# circuit.net
KiCad netlist of a schematic drawn in EAGLE
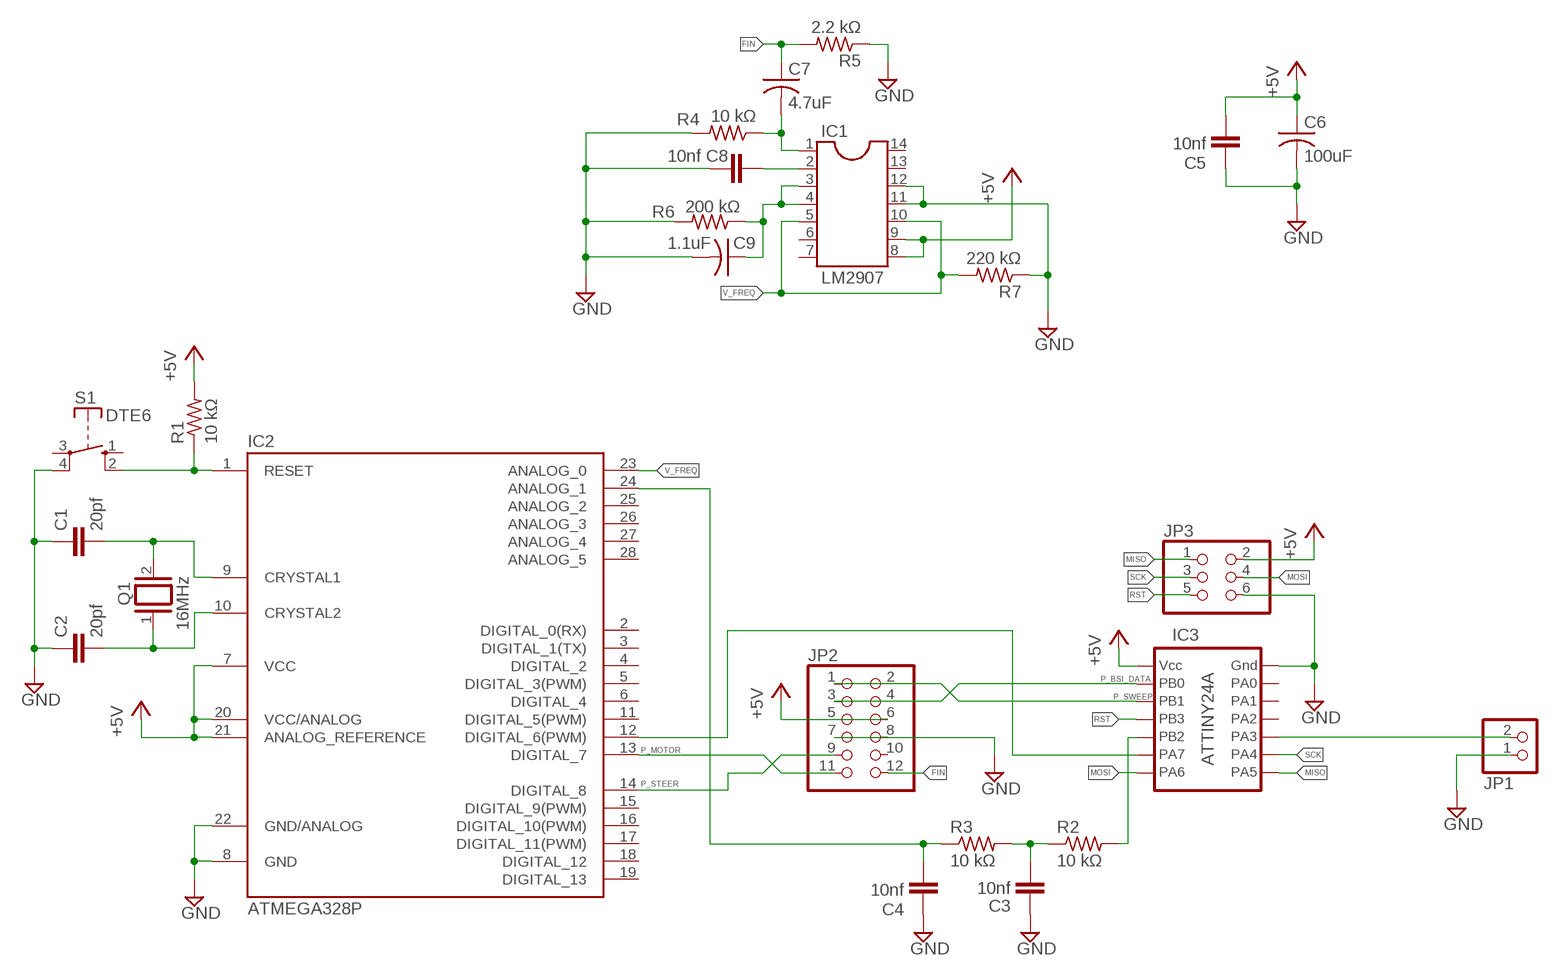
[diagram p0: schematic, sheet 1]

(export (version "E")
  (design (tool "Eeschema 10.0.6"))
  (components
    (comp (ref "C1")
      (value "20pf")
      (footprint "eagle-import:C025-024X044")
      (libsource (lib "eagle-import") (part "C-EU025-024X044"))
    )
    (comp (ref "C2")
      (value "20pf")
      (footprint "eagle-import:C025-024X044")
      (libsource (lib "eagle-import") (part "C-EU025-024X044"))
    )
    (comp (ref "C3")
      (value "10nf")
      (footprint "eagle-import:C025-024X044")
      (libsource (lib "eagle-import") (part "C-EU025-024X044"))
    )
    (comp (ref "C4")
      (value "10nf")
      (footprint "eagle-import:C025-024X044")
      (libsource (lib "eagle-import") (part "C-EU025-024X044"))
    )
    (comp (ref "C5")
      (value "10nf")
      (footprint "eagle-import:C025-024X044")
      (libsource (lib "eagle-import") (part "C-EU025-024X044"))
    )
    (comp (ref "C6")
      (value "100uF")
      (footprint "eagle-import:C025-050X050")
      (libsource (lib "eagle-import") (part "C-US025-050X050"))
    )
    (comp (ref "C7")
      (value "4.7uF")
      (footprint "eagle-import:C025-050X050")
      (libsource (lib "eagle-import") (part "C-US025-050X050"))
    )
    (comp (ref "C8")
      (value "10nf")
      (footprint "eagle-import:C025-024X044")
      (libsource (lib "eagle-import") (part "C-EU025-024X044"))
    )
    (comp (ref "C9")
      (value "1.1uF")
      (footprint "eagle-import:C025-050X050")
      (libsource (lib "eagle-import") (part "C-US025-050X050"))
    )
    (comp (ref "IC1")
      (value "LM2907")
      (footprint "eagle-import:DIL14")
      (libsource (lib "eagle-import") (part "DIL14"))
    )
    (comp (ref "IC2")
      (value "ATMEGA328P")
      (footprint "eagle-import:DIL28-3")
      (libsource (lib "eagle-import") (part "ATMEGA168-PU"))
    )
    (comp (ref "IC3")
      (value "ATTINY24A")
      (footprint "eagle-import:TINY24A")
      (libsource (lib "eagle-import") (part "ATTINY24A"))
    )
    (comp (ref "JP1")
      (value "PINHD-1X2")
      (footprint "eagle-import:1X02")
      (libsource (lib "eagle-import") (part "PINHD-1X2"))
    )
    (comp (ref "JP2")
      (value "PINHD-2X6")
      (footprint "eagle-import:2X06")
      (libsource (lib "eagle-import") (part "PINHD-2X6"))
    )
    (comp (ref "JP3")
      (value "PINHD-2X3")
      (footprint "eagle-import:2X03")
      (libsource (lib "eagle-import") (part "PINHD-2X3"))
    )
    (comp (ref "Q1")
      (value "16MHz")
      (footprint "eagle-import:QS")
      (libsource (lib "eagle-import") (part "XTAL/S"))
    )
    (comp (ref "R1")
      (value "10 kΩ")
      (footprint "eagle-import:0204V")
      (libsource (lib "eagle-import") (part "R-US_0204/2V"))
    )
    (comp (ref "R2")
      (value "10 kΩ")
      (footprint "eagle-import:0204V")
      (libsource (lib "eagle-import") (part "R-US_0204/2V"))
    )
    (comp (ref "R3")
      (value "10 kΩ")
      (footprint "eagle-import:0204V")
      (libsource (lib "eagle-import") (part "R-US_0204/2V"))
    )
    (comp (ref "R4")
      (value "10 kΩ")
      (footprint "eagle-import:0204V")
      (libsource (lib "eagle-import") (part "R-US_0204/2V"))
    )
    (comp (ref "R5")
      (value "2.2 kΩ")
      (footprint "eagle-import:0204V")
      (libsource (lib "eagle-import") (part "R-US_0204/2V"))
    )
    (comp (ref "R6")
      (value "200 kΩ")
      (footprint "eagle-import:0204V")
      (libsource (lib "eagle-import") (part "R-US_0204/2V"))
    )
    (comp (ref "R7")
      (value "220 kΩ")
      (footprint "eagle-import:0204V")
      (libsource (lib "eagle-import") (part "R-US_0204/2V"))
    )
    (comp (ref "S1")
      (value "DTE6")
      (footprint "eagle-import:DTE6")
      (libsource (lib "eagle-import") (part "DTE6"))
    )
  )
  (nets
    (net (code "1") (name "+5V") (class "Default")
      (node (ref "C5") (pin "2") (pinfunction "2_2") (pintype "passive"))
      (node (ref "C6") (pin "1") (pinfunction "1_1") (pintype "passive"))
      (node (ref "IC1") (pin "8") (pinfunction "8_8") (pintype "passive"))
      (node (ref "IC1") (pin "9") (pinfunction "9_9") (pintype "passive"))
      (node (ref "IC2") (pin "20") (pinfunction "VCC/ANALOG_20") (pintype "passive"))
      (node (ref "IC2") (pin "21") (pinfunction "ANALOG_REFERENCE_21") (pintype "passive"))
      (node (ref "IC2") (pin "7") (pinfunction "VCC_7") (pintype "power_in"))
      (node (ref "IC3") (pin "1") (pinfunction "P$1_1") (pintype "bidirectional"))
      (node (ref "JP2") (pin "5") (pinfunction "5_5") (pintype "passive"))
      (node (ref "JP2") (pin "6") (pinfunction "6_6") (pintype "passive"))
      (node (ref "JP3") (pin "2") (pinfunction "2_2") (pintype "passive"))
      (node (ref "R1") (pin "2") (pinfunction "2_2") (pintype "passive"))
    )
    (net (code "2") (name "/P_BSI_DATA") (class "Default")
      (node (ref "IC3") (pin "2") (pinfunction "P$2_2") (pintype "bidirectional"))
      (node (ref "JP2") (pin "3") (pinfunction "3_3") (pintype "passive"))
      (node (ref "JP2") (pin "4") (pinfunction "4_4") (pintype "passive"))
    )
    (net (code "3") (name "/P_MOTOR") (class "Default")
      (node (ref "IC2") (pin "13") (pinfunction "DIGITAL_7_13") (pintype "bidirectional"))
      (node (ref "JP2") (pin "11") (pinfunction "11_11") (pintype "passive"))
    )
    (net (code "4") (name "/P_STEER") (class "Default")
      (node (ref "IC2") (pin "14") (pinfunction "DIGITAL_8_14") (pintype "bidirectional"))
      (node (ref "JP2") (pin "9") (pinfunction "9_9") (pintype "passive"))
    )
    (net (code "5") (name "/P_SWEEP") (class "Default")
      (node (ref "IC3") (pin "3") (pinfunction "P$3_3") (pintype "bidirectional"))
      (node (ref "JP2") (pin "1") (pinfunction "1_1") (pintype "passive"))
      (node (ref "JP2") (pin "2") (pinfunction "2_2") (pintype "passive"))
    )
    (net (code "6") (name "FIN") (class "Default")
      (node (ref "C7") (pin "1") (pinfunction "1_1") (pintype "passive"))
      (node (ref "JP2") (pin "12") (pinfunction "12_12") (pintype "passive"))
      (node (ref "R5") (pin "2") (pinfunction "2_2") (pintype "passive"))
    )
    (net (code "7") (name "GND") (class "Default")
      (node (ref "C1") (pin "1") (pinfunction "1_1") (pintype "passive"))
      (node (ref "C2") (pin "1") (pinfunction "1_1") (pintype "passive"))
      (node (ref "C3") (pin "1") (pinfunction "1_1") (pintype "passive"))
      (node (ref "C4") (pin "1") (pinfunction "1_1") (pintype "passive"))
      (node (ref "C5") (pin "1") (pinfunction "1_1") (pintype "passive"))
      (node (ref "C6") (pin "2") (pinfunction "2_2") (pintype "passive"))
      (node (ref "C8") (pin "1") (pinfunction "1_1") (pintype "passive"))
      (node (ref "C9") (pin "2") (pinfunction "2_2") (pintype "passive"))
      (node (ref "IC1") (pin "11") (pinfunction "11_11") (pintype "passive"))
      (node (ref "IC1") (pin "12") (pinfunction "12_12") (pintype "passive"))
      (node (ref "IC2") (pin "22") (pinfunction "GND/ANALOG_22") (pintype "power_in"))
      (node (ref "IC2") (pin "8") (pinfunction "GND_8") (pintype "power_in"))
      (node (ref "IC3") (pin "14") (pinfunction "P$14_14") (pintype "bidirectional"))
      (node (ref "JP1") (pin "1") (pinfunction "1_1") (pintype "passive"))
      (node (ref "JP2") (pin "7") (pinfunction "7_7") (pintype "passive"))
      (node (ref "JP2") (pin "8") (pinfunction "8_8") (pintype "passive"))
      (node (ref "JP3") (pin "6") (pinfunction "6_6") (pintype "passive"))
      (node (ref "R4") (pin "2") (pinfunction "2_2") (pintype "passive"))
      (node (ref "R5") (pin "1") (pinfunction "1_1") (pintype "passive"))
      (node (ref "R6") (pin "2") (pinfunction "2_2") (pintype "passive"))
      (node (ref "R7") (pin "1") (pinfunction "1_1") (pintype "passive"))
      (node (ref "S1") (pin "4") (pinfunction "P_4") (pintype "passive"))
    )
    (net (code "8") (name "MISO") (class "Default")
      (node (ref "IC3") (pin "8") (pinfunction "P$8_8") (pintype "bidirectional"))
      (node (ref "JP3") (pin "1") (pinfunction "1_1") (pintype "passive"))
    )
    (net (code "9") (name "MOSI") (class "Default")
      (node (ref "IC3") (pin "7") (pinfunction "P$7_7") (pintype "bidirectional"))
      (node (ref "JP3") (pin "4") (pinfunction "4_4") (pintype "passive"))
    )
    (net (code "10") (name "Net-(C3-Pad2)") (class "Default")
      (node (ref "C3") (pin "2") (pinfunction "2_2") (pintype "passive"))
      (node (ref "R2") (pin "1") (pinfunction "1_1") (pintype "passive"))
      (node (ref "R3") (pin "2") (pinfunction "2_2") (pintype "passive"))
    )
    (net (code "11") (name "Net-(C7-Pad2)") (class "Default")
      (node (ref "C7") (pin "2") (pinfunction "2_2") (pintype "passive"))
      (node (ref "IC1") (pin "1") (pinfunction "1_1") (pintype "passive"))
      (node (ref "R4") (pin "1") (pinfunction "1_1") (pintype "passive"))
    )
    (net (code "12") (name "Net-(C8-Pad2)") (class "Default")
      (node (ref "C8") (pin "2") (pinfunction "2_2") (pintype "passive"))
      (node (ref "IC1") (pin "2") (pinfunction "2_2") (pintype "passive"))
    )
    (net (code "13") (name "Net-(C9-Pad1)") (class "Default")
      (node (ref "C9") (pin "1") (pinfunction "1_1") (pintype "passive"))
      (node (ref "IC1") (pin "3") (pinfunction "3_3") (pintype "passive"))
      (node (ref "IC1") (pin "4") (pinfunction "4_4") (pintype "passive"))
      (node (ref "R6") (pin "1") (pinfunction "1_1") (pintype "passive"))
    )
    (net (code "14") (name "Net-(IC2-ANALOG_1)") (class "Default")
      (node (ref "C4") (pin "2") (pinfunction "2_2") (pintype "passive"))
      (node (ref "IC2") (pin "24") (pinfunction "ANALOG_1_24") (pintype "bidirectional"))
      (node (ref "R3") (pin "1") (pinfunction "1_1") (pintype "passive"))
    )
    (net (code "15") (name "Net-(IC2-CRYSTAL1)") (class "Default")
      (node (ref "C1") (pin "2") (pinfunction "2_2") (pintype "passive"))
      (node (ref "IC2") (pin "9") (pinfunction "CRYSTAL1_9") (pintype "bidirectional"))
      (node (ref "Q1") (pin "2") (pinfunction "2_2") (pintype "passive"))
    )
    (net (code "16") (name "Net-(IC2-CRYSTAL2)") (class "Default")
      (node (ref "C2") (pin "2") (pinfunction "2_2") (pintype "passive"))
      (node (ref "IC2") (pin "10") (pinfunction "CRYSTAL2_10") (pintype "bidirectional"))
      (node (ref "Q1") (pin "1") (pinfunction "1_1") (pintype "passive"))
    )
    (net (code "17") (name "Net-(IC2-DIGITAL_6(PWM))") (class "Default")
      (node (ref "IC2") (pin "12") (pinfunction "DIGITAL_6(PWM)_12") (pintype "bidirectional"))
      (node (ref "IC3") (pin "6") (pinfunction "P$6_6") (pintype "bidirectional"))
    )
    (net (code "18") (name "Net-(IC2-RESET)") (class "Default")
      (node (ref "IC2") (pin "1") (pinfunction "RESET_1") (pintype "bidirectional"))
      (node (ref "R1") (pin "1") (pinfunction "1_1") (pintype "passive"))
      (node (ref "S1") (pin "2") (pinfunction "S_2") (pintype "passive"))
    )
    (net (code "19") (name "Net-(IC3-P$5)") (class "Default")
      (node (ref "IC3") (pin "5") (pinfunction "P$5_5") (pintype "bidirectional"))
      (node (ref "R2") (pin "2") (pinfunction "2_2") (pintype "passive"))
    )
    (net (code "20") (name "Net-(IC3-P$10)") (class "Default")
      (node (ref "IC3") (pin "10") (pinfunction "P$10_10") (pintype "bidirectional"))
      (node (ref "JP1") (pin "2") (pinfunction "2_2") (pintype "passive"))
    )
    (net (code "21") (name "RST") (class "Default")
      (node (ref "IC3") (pin "4") (pinfunction "P$4_4") (pintype "bidirectional"))
      (node (ref "JP3") (pin "5") (pinfunction "5_5") (pintype "passive"))
    )
    (net (code "22") (name "SCK") (class "Default")
      (node (ref "IC3") (pin "9") (pinfunction "P$9_9") (pintype "bidirectional"))
      (node (ref "JP3") (pin "3") (pinfunction "3_3") (pintype "passive"))
    )
    (net (code "23") (name "V_FREQ") (class "Default")
      (node (ref "IC1") (pin "10") (pinfunction "10_10") (pintype "passive"))
      (node (ref "IC1") (pin "5") (pinfunction "5_5") (pintype "passive"))
      (node (ref "IC2") (pin "23") (pinfunction "ANALOG_0_23") (pintype "bidirectional"))
      (node (ref "R7") (pin "2") (pinfunction "2_2") (pintype "passive"))
    )
    (net (code "24") (name "unconnected-(IC1-Pad6)") (class "Default")
      (node (ref "IC1") (pin "6") (pinfunction "6_6") (pintype "passive"))
    )
    (net (code "25") (name "unconnected-(IC1-Pad7)") (class "Default")
      (node (ref "IC1") (pin "7") (pinfunction "7_7") (pintype "passive"))
    )
    (net (code "26") (name "unconnected-(IC1-Pad13)") (class "Default")
      (node (ref "IC1") (pin "13") (pinfunction "13_13") (pintype "passive"))
    )
    (net (code "27") (name "unconnected-(IC1-Pad14)") (class "Default")
      (node (ref "IC1") (pin "14") (pinfunction "14_14") (pintype "passive"))
    )
    (net (code "28") (name "unconnected-(IC2-ANALOG_2-Pad25)") (class "Default")
      (node (ref "IC2") (pin "25") (pinfunction "ANALOG_2_25") (pintype "bidirectional"))
    )
    (net (code "29") (name "unconnected-(IC2-ANALOG_3-Pad26)") (class "Default")
      (node (ref "IC2") (pin "26") (pinfunction "ANALOG_3_26") (pintype "bidirectional"))
    )
    (net (code "30") (name "unconnected-(IC2-ANALOG_4-Pad27)") (class "Default")
      (node (ref "IC2") (pin "27") (pinfunction "ANALOG_4_27") (pintype "bidirectional"))
    )
    (net (code "31") (name "unconnected-(IC2-ANALOG_5-Pad28)") (class "Default")
      (node (ref "IC2") (pin "28") (pinfunction "ANALOG_5_28") (pintype "bidirectional"))
    )
    (net (code "32") (name "unconnected-(IC2-DIGITAL_0(RX)-Pad2)") (class "Default")
      (node (ref "IC2") (pin "2") (pinfunction "DIGITAL_0(RX)_2") (pintype "bidirectional"))
    )
    (net (code "33") (name "unconnected-(IC2-DIGITAL_1(TX)-Pad3)") (class "Default")
      (node (ref "IC2") (pin "3") (pinfunction "DIGITAL_1(TX)_3") (pintype "bidirectional"))
    )
    (net (code "34") (name "unconnected-(IC2-DIGITAL_2-Pad4)") (class "Default")
      (node (ref "IC2") (pin "4") (pinfunction "DIGITAL_2_4") (pintype "bidirectional"))
    )
    (net (code "35") (name "unconnected-(IC2-DIGITAL_3(PWM)-Pad5)") (class "Default")
      (node (ref "IC2") (pin "5") (pinfunction "DIGITAL_3(PWM)_5") (pintype "bidirectional"))
    )
    (net (code "36") (name "unconnected-(IC2-DIGITAL_4-Pad6)") (class "Default")
      (node (ref "IC2") (pin "6") (pinfunction "DIGITAL_4_6") (pintype "bidirectional"))
    )
    (net (code "37") (name "unconnected-(IC2-DIGITAL_5(PWM)-Pad11)") (class "Default")
      (node (ref "IC2") (pin "11") (pinfunction "DIGITAL_5(PWM)_11") (pintype "bidirectional"))
    )
    (net (code "38") (name "unconnected-(IC2-DIGITAL_9(PWM)-Pad15)") (class "Default")
      (node (ref "IC2") (pin "15") (pinfunction "DIGITAL_9(PWM)_15") (pintype "bidirectional"))
    )
    (net (code "39") (name "unconnected-(IC2-DIGITAL_10(PWM)-Pad16)") (class "Default")
      (node (ref "IC2") (pin "16") (pinfunction "DIGITAL_10(PWM)_16") (pintype "bidirectional"))
    )
    (net (code "40") (name "unconnected-(IC2-DIGITAL_11(PWM)-Pad17)") (class "Default")
      (node (ref "IC2") (pin "17") (pinfunction "DIGITAL_11(PWM)_17") (pintype "bidirectional"))
    )
    (net (code "41") (name "unconnected-(IC2-DIGITAL_12-Pad18)") (class "Default")
      (node (ref "IC2") (pin "18") (pinfunction "DIGITAL_12_18") (pintype "bidirectional"))
    )
    (net (code "42") (name "unconnected-(IC2-DIGITAL_13-Pad19)") (class "Default")
      (node (ref "IC2") (pin "19") (pinfunction "DIGITAL_13_19") (pintype "bidirectional"))
    )
    (net (code "43") (name "unconnected-(IC3-P$11-Pad11)") (class "Default")
      (node (ref "IC3") (pin "11") (pinfunction "P$11_11") (pintype "bidirectional"))
    )
    (net (code "44") (name "unconnected-(IC3-P$12-Pad12)") (class "Default")
      (node (ref "IC3") (pin "12") (pinfunction "P$12_12") (pintype "bidirectional"))
    )
    (net (code "45") (name "unconnected-(IC3-P$13-Pad13)") (class "Default")
      (node (ref "IC3") (pin "13") (pinfunction "P$13_13") (pintype "bidirectional"))
    )
    (net (code "46") (name "unconnected-(JP2-Pad10)") (class "Default")
      (node (ref "JP2") (pin "10") (pinfunction "10_10") (pintype "passive"))
    )
    (net (code "47") (name "unconnected-(S1-P-Pad3)") (class "Default")
      (node (ref "S1") (pin "3") (pinfunction "P_3") (pintype "passive"))
    )
    (net (code "48") (name "unconnected-(S1-S-Pad1)") (class "Default")
      (node (ref "S1") (pin "1") (pinfunction "S_1") (pintype "passive"))
    )
  )
)
